# secondary_EEPROM_and_T.net
KiCad netlist of a schematic drawn in Altium Designer
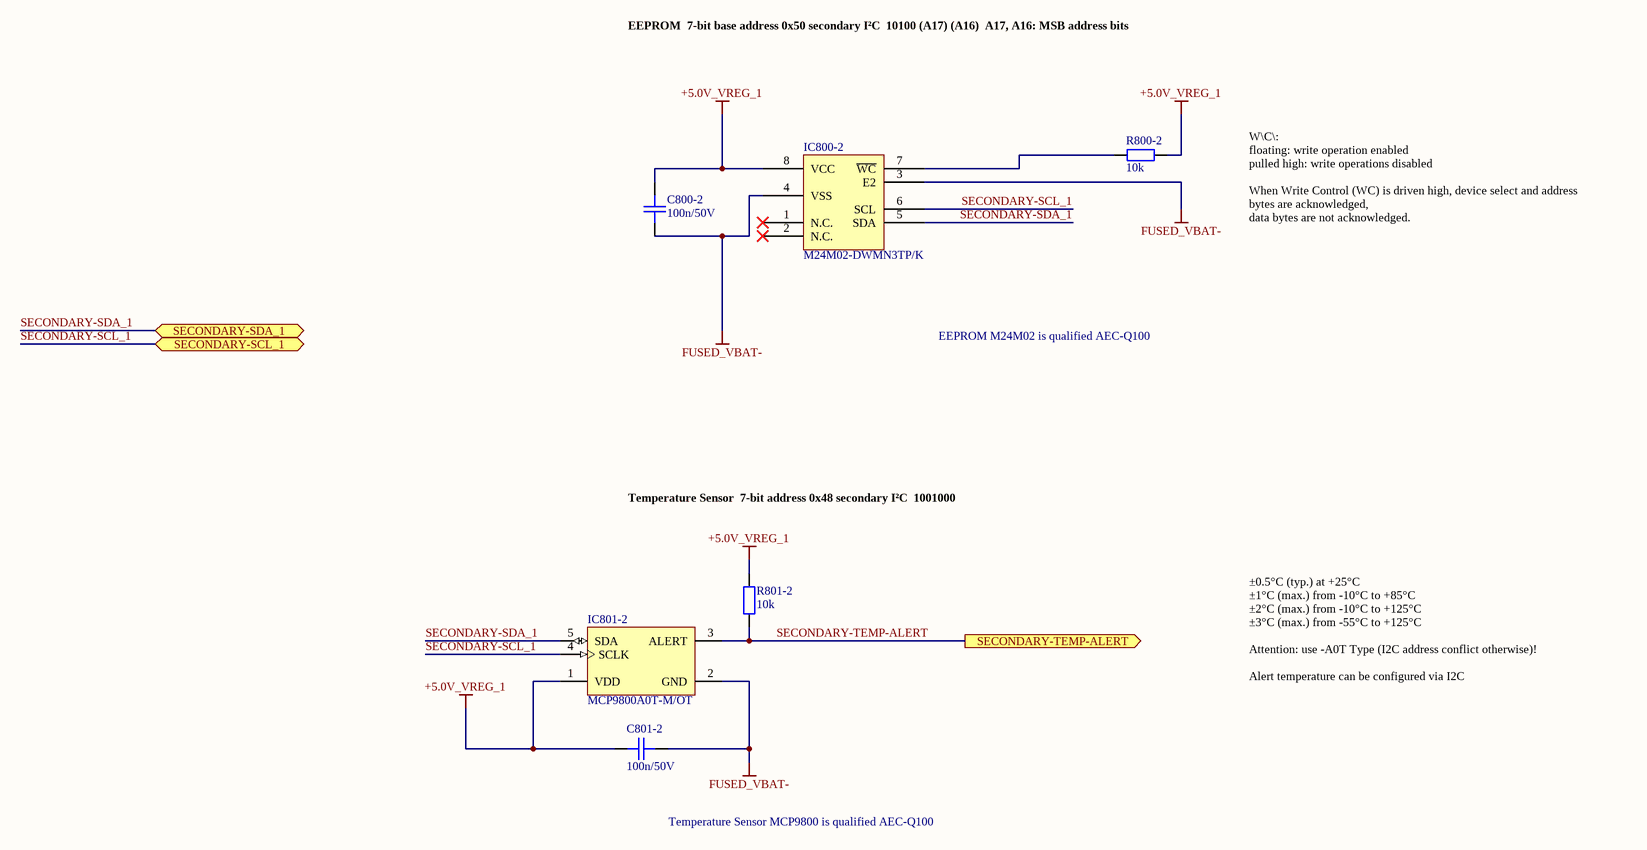
[diagram p0: secondary_EEPROM_and_T.SchDoc]

(export (version "E")
  (design (tool "Eeschema 10.0.6"))
  (components
    (comp (ref "C800-2")
      (value "100n/50V")
      (footprint "CAPC1608X08N")
      (description "MLCC")
      (fields (field (name "PART NUMBER") "gen_C_ceramic_100n_50V_X7R_0603"))
      (libsource (lib "OE750") (part "C"))
    )
    (comp (ref "C801-2")
      (value "100n/50V")
      (footprint "CAPC1608X08N")
      (description "MLCC")
      (fields (field (name "PART NUMBER") "gen_C_ceramic_100n_50V_X7R_0603"))
      (libsource (lib "OE750") (part "C"))
    )
    (comp (ref "IC800-2")
      (value "M24M02-DWMN3TP/K")
      (footprint "SOIC127P600X175-8N")
      (description "Automotive 2-Mbit serial I²C \r\nbus EEPROM with 1 MHz clock")
      (fields (field (name "MANUFACTURER") "STMicroelectronics"))
      (libsource (lib "OE750") (part "M24M02-DWMN3TP/K"))
    )
    (comp (ref "IC801-2")
      (value "MCP9800A0T-M/OT")
      (footprint "SOT-23-OT5_L")
      (libsource (lib "Altium Content Vault") (part "SEN-TEMP-MCP980X-5"))
    )
    (comp (ref "R800-2")
      (value "10k")
      (footprint "RESC1608X05N")
      (description "SMD Resistor 10k 0603")
      (fields (field (name "PART NUMBER") "gen_R_10k_0603") (field (name "TOLERANCE") "1%"))
      (libsource (lib "OE750") (part "R"))
    )
    (comp (ref "R801-2")
      (value "10k")
      (footprint "RESC1608X05N")
      (description "SMD Resistor 10k 0603")
      (fields (field (name "PART NUMBER") "gen_R_10k_0603") (field (name "TOLERANCE") "1%"))
      (libsource (lib "OE750") (part "R"))
    )
  )
  (nets
    (net (code "1") (name "+5.0V_VREG_1") (class "Default")
      (node (ref "C800-2") (pin "2") (pinfunction "2_2") (pintype "passive"))
      (node (ref "C801-2") (pin "2") (pinfunction "2_2") (pintype "passive"))
      (node (ref "IC800-2") (pin "8") (pinfunction "VCC_8") (pintype "power_in"))
      (node (ref "IC801-2") (pin "1") (pinfunction "VDD_1") (pintype "power_in"))
      (node (ref "R800-2") (pin "2") (pinfunction "2_2") (pintype "passive"))
      (node (ref "R801-2") (pin "2") (pinfunction "2_2") (pintype "passive"))
    )
    (net (code "2") (name "/SECONDARY-SCL_1") (class "Default")
      (node (ref "IC800-2") (pin "6") (pinfunction "SCL_6") (pintype "passive"))
      (node (ref "IC801-2") (pin "4") (pinfunction "SCLK_4") (pintype "input"))
    )
    (net (code "3") (name "/SECONDARY-SDA_1") (class "Default")
      (node (ref "IC800-2") (pin "5") (pinfunction "SDA_5") (pintype "passive"))
      (node (ref "IC801-2") (pin "5") (pinfunction "SDA_5") (pintype "bidirectional"))
    )
    (net (code "4") (name "/SECONDARY-TEMP-ALERT") (class "Default")
      (node (ref "IC801-2") (pin "3") (pinfunction "ALERT_3") (pintype "open_collector"))
      (node (ref "R801-2") (pin "1") (pinfunction "1_1") (pintype "passive"))
    )
    (net (code "5") (name "FUSED_VBAT-") (class "Default")
      (node (ref "C800-2") (pin "1") (pinfunction "1_1") (pintype "passive"))
      (node (ref "C801-2") (pin "1") (pinfunction "1_1") (pintype "passive"))
      (node (ref "IC800-2") (pin "3") (pinfunction "E2_3") (pintype "passive"))
      (node (ref "IC800-2") (pin "4") (pinfunction "VSS_4") (pintype "power_in"))
      (node (ref "IC801-2") (pin "2") (pinfunction "GND_2") (pintype "power_in"))
    )
    (net (code "6") (name "Net-(IC800-2-~{WC})") (class "Default")
      (node (ref "IC800-2") (pin "7") (pinfunction "~{WC}_7") (pintype "passive"))
      (node (ref "R800-2") (pin "1") (pinfunction "1_1") (pintype "passive"))
    )
    (net (code "7") (name "unconnected-(IC800-2-N.C.-Pad1)") (class "Default")
      (node (ref "IC800-2") (pin "1") (pinfunction "N.C._1") (pintype "passive+no_connect"))
    )
    (net (code "8") (name "unconnected-(IC800-2-N.C.-Pad2)") (class "Default")
      (node (ref "IC800-2") (pin "2") (pinfunction "N.C._2") (pintype "passive+no_connect"))
    )
  )
)
